# SensorMCU.net
KiCad netlist of a schematic drawn in Altium Designer
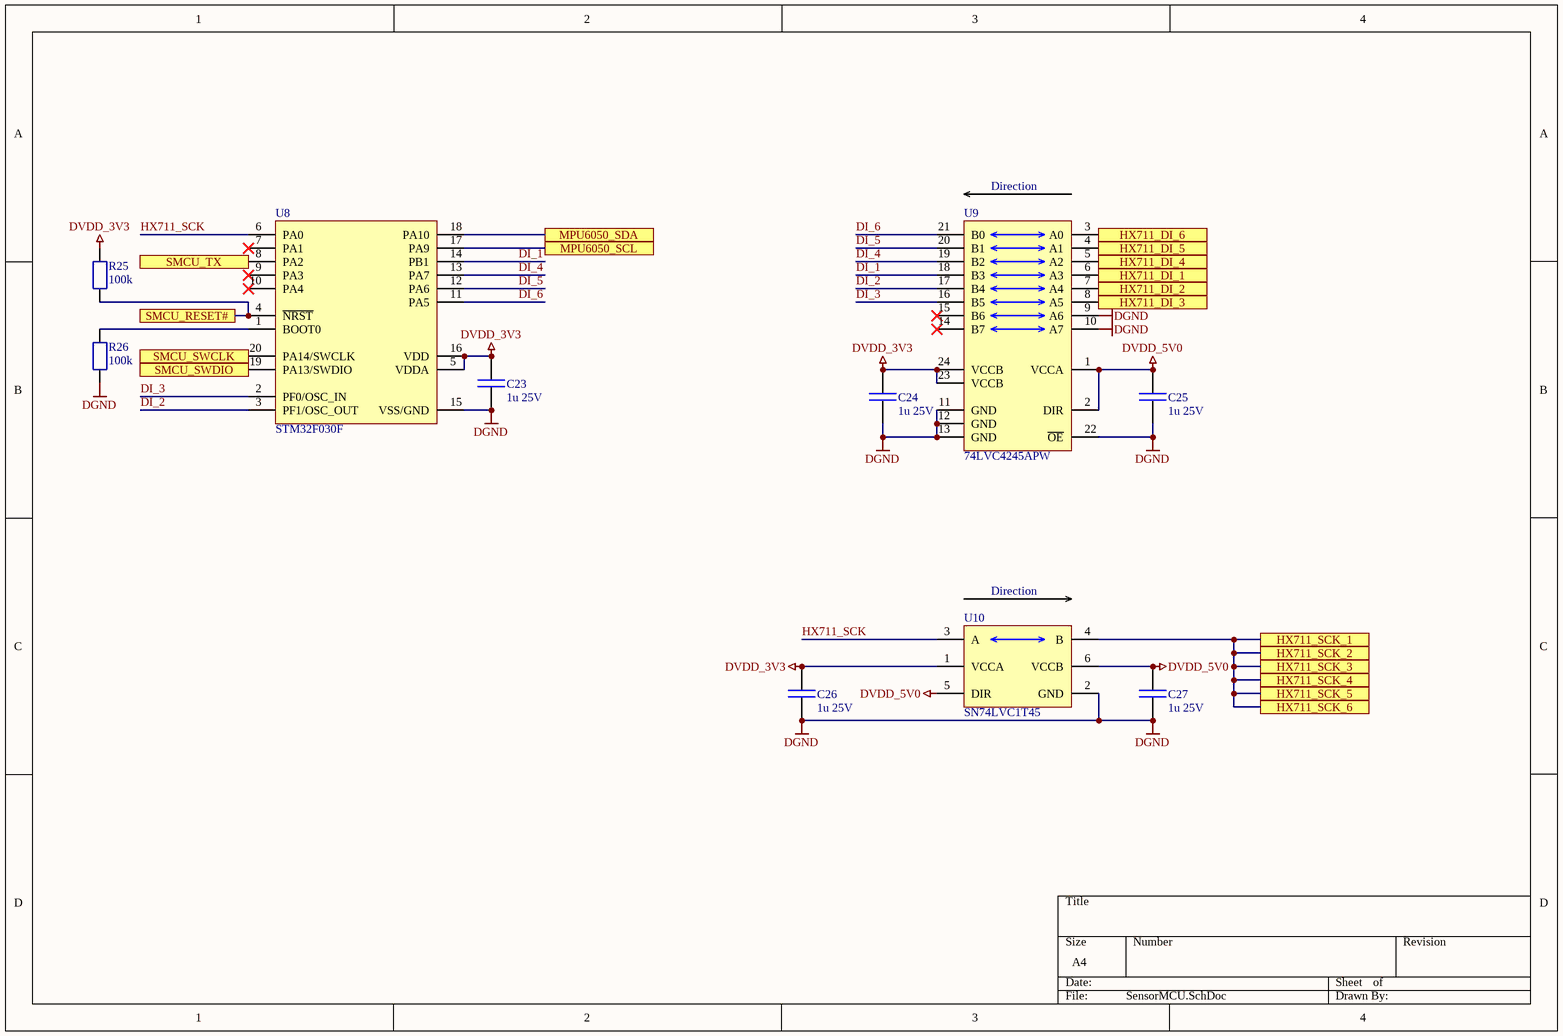
[diagram p0: SensorMCU.SchDoc]

(export (version "E")
  (design (tool "Eeschema 10.0.6"))
  (components
    (comp (ref "C23")
      (value "1u 25V")
      (footprint "C_0603/1608")
      (description "Non-polarized capacitor")
      (libsource (lib "passive") (part "Capacitor"))
    )
    (comp (ref "C24")
      (value "1u 25V")
      (footprint "C_0603/1608")
      (description "Non-polarized capacitor")
      (libsource (lib "passive") (part "Capacitor"))
    )
    (comp (ref "C25")
      (value "1u 25V")
      (footprint "C_0603/1608")
      (description "Non-polarized capacitor")
      (libsource (lib "passive") (part "Capacitor"))
    )
    (comp (ref "C26")
      (value "1u 25V")
      (footprint "C_0603/1608")
      (description "Non-polarized capacitor")
      (libsource (lib "passive") (part "Capacitor"))
    )
    (comp (ref "C27")
      (value "1u 25V")
      (footprint "C_0603/1608")
      (description "Non-polarized capacitor")
      (libsource (lib "passive") (part "Capacitor"))
    )
    (comp (ref "R25")
      (value "100k")
      (footprint "R_0603/1608")
      (description "Resistor")
      (libsource (lib "passive") (part "Resistor"))
    )
    (comp (ref "R26")
      (value "100k")
      (footprint "R_0603/1608")
      (description "Resistor")
      (libsource (lib "passive") (part "Resistor"))
    )
    (comp (ref "U8")
      (value "STM32F030F")
      (footprint "SO20_0.65")
      (description "32-bit Cortex-M0")
      (libsource (lib "MCU and memory") (part "STM32F030F"))
    )
    (comp (ref "U9")
      (value "74LVC4245APW")
      (footprint "SO24_0.65")
      (description "Logic level converter")
      (libsource (lib "digital") (part "74LVC4245APW"))
    )
    (comp (ref "U10")
      (value "SN74LVC1T45")
      (footprint "SOT23-6")
      (description "Logic level converter")
      (libsource (lib "digital") (part "SN74LVC1T45"))
    )
  )
  (nets
    (net (code "1") (name "/DI_1") (class "Default")
      (node (ref "U8") (pin "14") (pinfunction "PB1_14") (pintype "passive"))
      (node (ref "U9") (pin "18") (pinfunction "B3_18") (pintype "passive"))
    )
    (net (code "2") (name "/DI_2") (class "Default")
      (node (ref "U8") (pin "3") (pinfunction "PF1/OSC_OUT_3") (pintype "passive"))
      (node (ref "U9") (pin "17") (pinfunction "B4_17") (pintype "passive"))
    )
    (net (code "3") (name "/DI_3") (class "Default")
      (node (ref "U8") (pin "2") (pinfunction "PF0/OSC_IN_2") (pintype "passive"))
      (node (ref "U9") (pin "16") (pinfunction "B5_16") (pintype "passive"))
    )
    (net (code "4") (name "/DI_4") (class "Default")
      (node (ref "U8") (pin "13") (pinfunction "PA7_13") (pintype "passive"))
      (node (ref "U9") (pin "19") (pinfunction "B2_19") (pintype "passive"))
    )
    (net (code "5") (name "/DI_5") (class "Default")
      (node (ref "U8") (pin "12") (pinfunction "PA6_12") (pintype "passive"))
      (node (ref "U9") (pin "20") (pinfunction "B1_20") (pintype "passive"))
    )
    (net (code "6") (name "/DI_6") (class "Default")
      (node (ref "U8") (pin "11") (pinfunction "PA5_11") (pintype "passive"))
      (node (ref "U9") (pin "21") (pinfunction "B0_21") (pintype "passive"))
    )
    (net (code "7") (name "/HX711_DI_1") (class "Default")
      (node (ref "U9") (pin "6") (pinfunction "A3_6") (pintype "passive"))
    )
    (net (code "8") (name "/HX711_DI_2") (class "Default")
      (node (ref "U9") (pin "7") (pinfunction "A4_7") (pintype "passive"))
    )
    (net (code "9") (name "/HX711_DI_3") (class "Default")
      (node (ref "U9") (pin "8") (pinfunction "A5_8") (pintype "passive"))
    )
    (net (code "10") (name "/HX711_DI_4") (class "Default")
      (node (ref "U9") (pin "5") (pinfunction "A2_5") (pintype "passive"))
    )
    (net (code "11") (name "/HX711_DI_5") (class "Default")
      (node (ref "U9") (pin "4") (pinfunction "A1_4") (pintype "passive"))
    )
    (net (code "12") (name "/HX711_DI_6") (class "Default")
      (node (ref "U9") (pin "3") (pinfunction "A0_3") (pintype "passive"))
    )
    (net (code "13") (name "/HX711_SCK") (class "Default")
      (node (ref "U10") (pin "3") (pinfunction "A_3") (pintype "passive"))
      (node (ref "U8") (pin "6") (pinfunction "PA0_6") (pintype "passive"))
    )
    (net (code "14") (name "/HX711_SCK_1") (class "Default")
      (node (ref "U10") (pin "4") (pinfunction "B_4") (pintype "passive"))
    )
    (net (code "15") (name "/MPU6050_SCL") (class "Default")
      (node (ref "U8") (pin "17") (pinfunction "PA9_17") (pintype "passive"))
    )
    (net (code "16") (name "/MPU6050_SDA") (class "Default")
      (node (ref "U8") (pin "18") (pinfunction "PA10_18") (pintype "passive"))
    )
    (net (code "17") (name "/SMCU_RESET#") (class "Default")
      (node (ref "R25") (pin "2") (pintype "passive"))
      (node (ref "U8") (pin "4") (pinfunction "~{NRST}_4") (pintype "passive"))
    )
    (net (code "18") (name "/SMCU_SWCLK") (class "Default")
      (node (ref "U8") (pin "20") (pinfunction "PA14/SWCLK_20") (pintype "passive"))
    )
    (net (code "19") (name "/SMCU_SWDIO") (class "Default")
      (node (ref "U8") (pin "19") (pinfunction "PA13/SWDIO_19") (pintype "passive"))
    )
    (net (code "20") (name "/SMCU_TX") (class "Default")
      (node (ref "U8") (pin "8") (pinfunction "PA2_8") (pintype "passive"))
    )
    (net (code "21") (name "DGND") (class "Default")
      (node (ref "C23") (pin "2") (pintype "passive"))
      (node (ref "C24") (pin "2") (pintype "passive"))
      (node (ref "C25") (pin "2") (pintype "passive"))
      (node (ref "C26") (pin "2") (pintype "passive"))
      (node (ref "C27") (pin "2") (pintype "passive"))
      (node (ref "R26") (pin "2") (pintype "passive"))
      (node (ref "U10") (pin "2") (pinfunction "GND_2") (pintype "passive"))
      (node (ref "U8") (pin "15") (pinfunction "VSS/GND_15") (pintype "passive"))
      (node (ref "U9") (pin "10") (pinfunction "A7_10") (pintype "passive"))
      (node (ref "U9") (pin "11") (pinfunction "GND_11") (pintype "passive"))
      (node (ref "U9") (pin "12") (pinfunction "GND_12") (pintype "passive"))
      (node (ref "U9") (pin "13") (pinfunction "GND_13") (pintype "passive"))
      (node (ref "U9") (pin "22") (pinfunction "~{OE}_22") (pintype "passive"))
      (node (ref "U9") (pin "9") (pinfunction "A6_9") (pintype "passive"))
    )
    (net (code "22") (name "DVDD_3V3") (class "Default")
      (node (ref "C23") (pin "1") (pintype "passive"))
      (node (ref "C24") (pin "1") (pintype "passive"))
      (node (ref "C26") (pin "1") (pintype "passive"))
      (node (ref "R25") (pin "1") (pintype "passive"))
      (node (ref "U10") (pin "1") (pinfunction "VCCA_1") (pintype "passive"))
      (node (ref "U8") (pin "16") (pinfunction "VDD_16") (pintype "passive"))
      (node (ref "U8") (pin "5") (pinfunction "VDDA_5") (pintype "passive"))
      (node (ref "U9") (pin "23") (pinfunction "VCCB_23") (pintype "passive"))
      (node (ref "U9") (pin "24") (pinfunction "VCCB_24") (pintype "passive"))
    )
    (net (code "23") (name "DVDD_5V0") (class "Default")
      (node (ref "C25") (pin "1") (pintype "passive"))
      (node (ref "C27") (pin "1") (pintype "passive"))
      (node (ref "U10") (pin "5") (pinfunction "DIR_5") (pintype "passive"))
      (node (ref "U10") (pin "6") (pinfunction "VCCB_6") (pintype "passive"))
      (node (ref "U9") (pin "1") (pinfunction "VCCA_1") (pintype "passive"))
      (node (ref "U9") (pin "2") (pinfunction "DIR_2") (pintype "passive"))
    )
    (net (code "24") (name "Net-(U8-BOOT0)") (class "Default")
      (node (ref "R26") (pin "1") (pintype "passive"))
      (node (ref "U8") (pin "1") (pinfunction "BOOT0_1") (pintype "passive"))
    )
    (net (code "25") (name "unconnected-(U8-EP-Pad0)") (class "Default")
      (node (ref "U8") (pin "0") (pinfunction "EP_0") (pintype "passive"))
    )
    (net (code "26") (name "unconnected-(U8-PA1-Pad7)") (class "Default")
      (node (ref "U8") (pin "7") (pinfunction "PA1_7") (pintype "passive+no_connect"))
    )
    (net (code "27") (name "unconnected-(U8-PA3-Pad9)") (class "Default")
      (node (ref "U8") (pin "9") (pinfunction "PA3_9") (pintype "passive+no_connect"))
    )
    (net (code "28") (name "unconnected-(U8-PA4-Pad10)") (class "Default")
      (node (ref "U8") (pin "10") (pinfunction "PA4_10") (pintype "passive+no_connect"))
    )
    (net (code "29") (name "unconnected-(U9-B6-Pad15)") (class "Default")
      (node (ref "U9") (pin "15") (pinfunction "B6_15") (pintype "passive+no_connect"))
    )
    (net (code "30") (name "unconnected-(U9-B7-Pad14)") (class "Default")
      (node (ref "U9") (pin "14") (pinfunction "B7_14") (pintype "passive+no_connect"))
    )
  )
)
